# Sheet1.net
KiCad netlist of a schematic drawn in Altium Designer
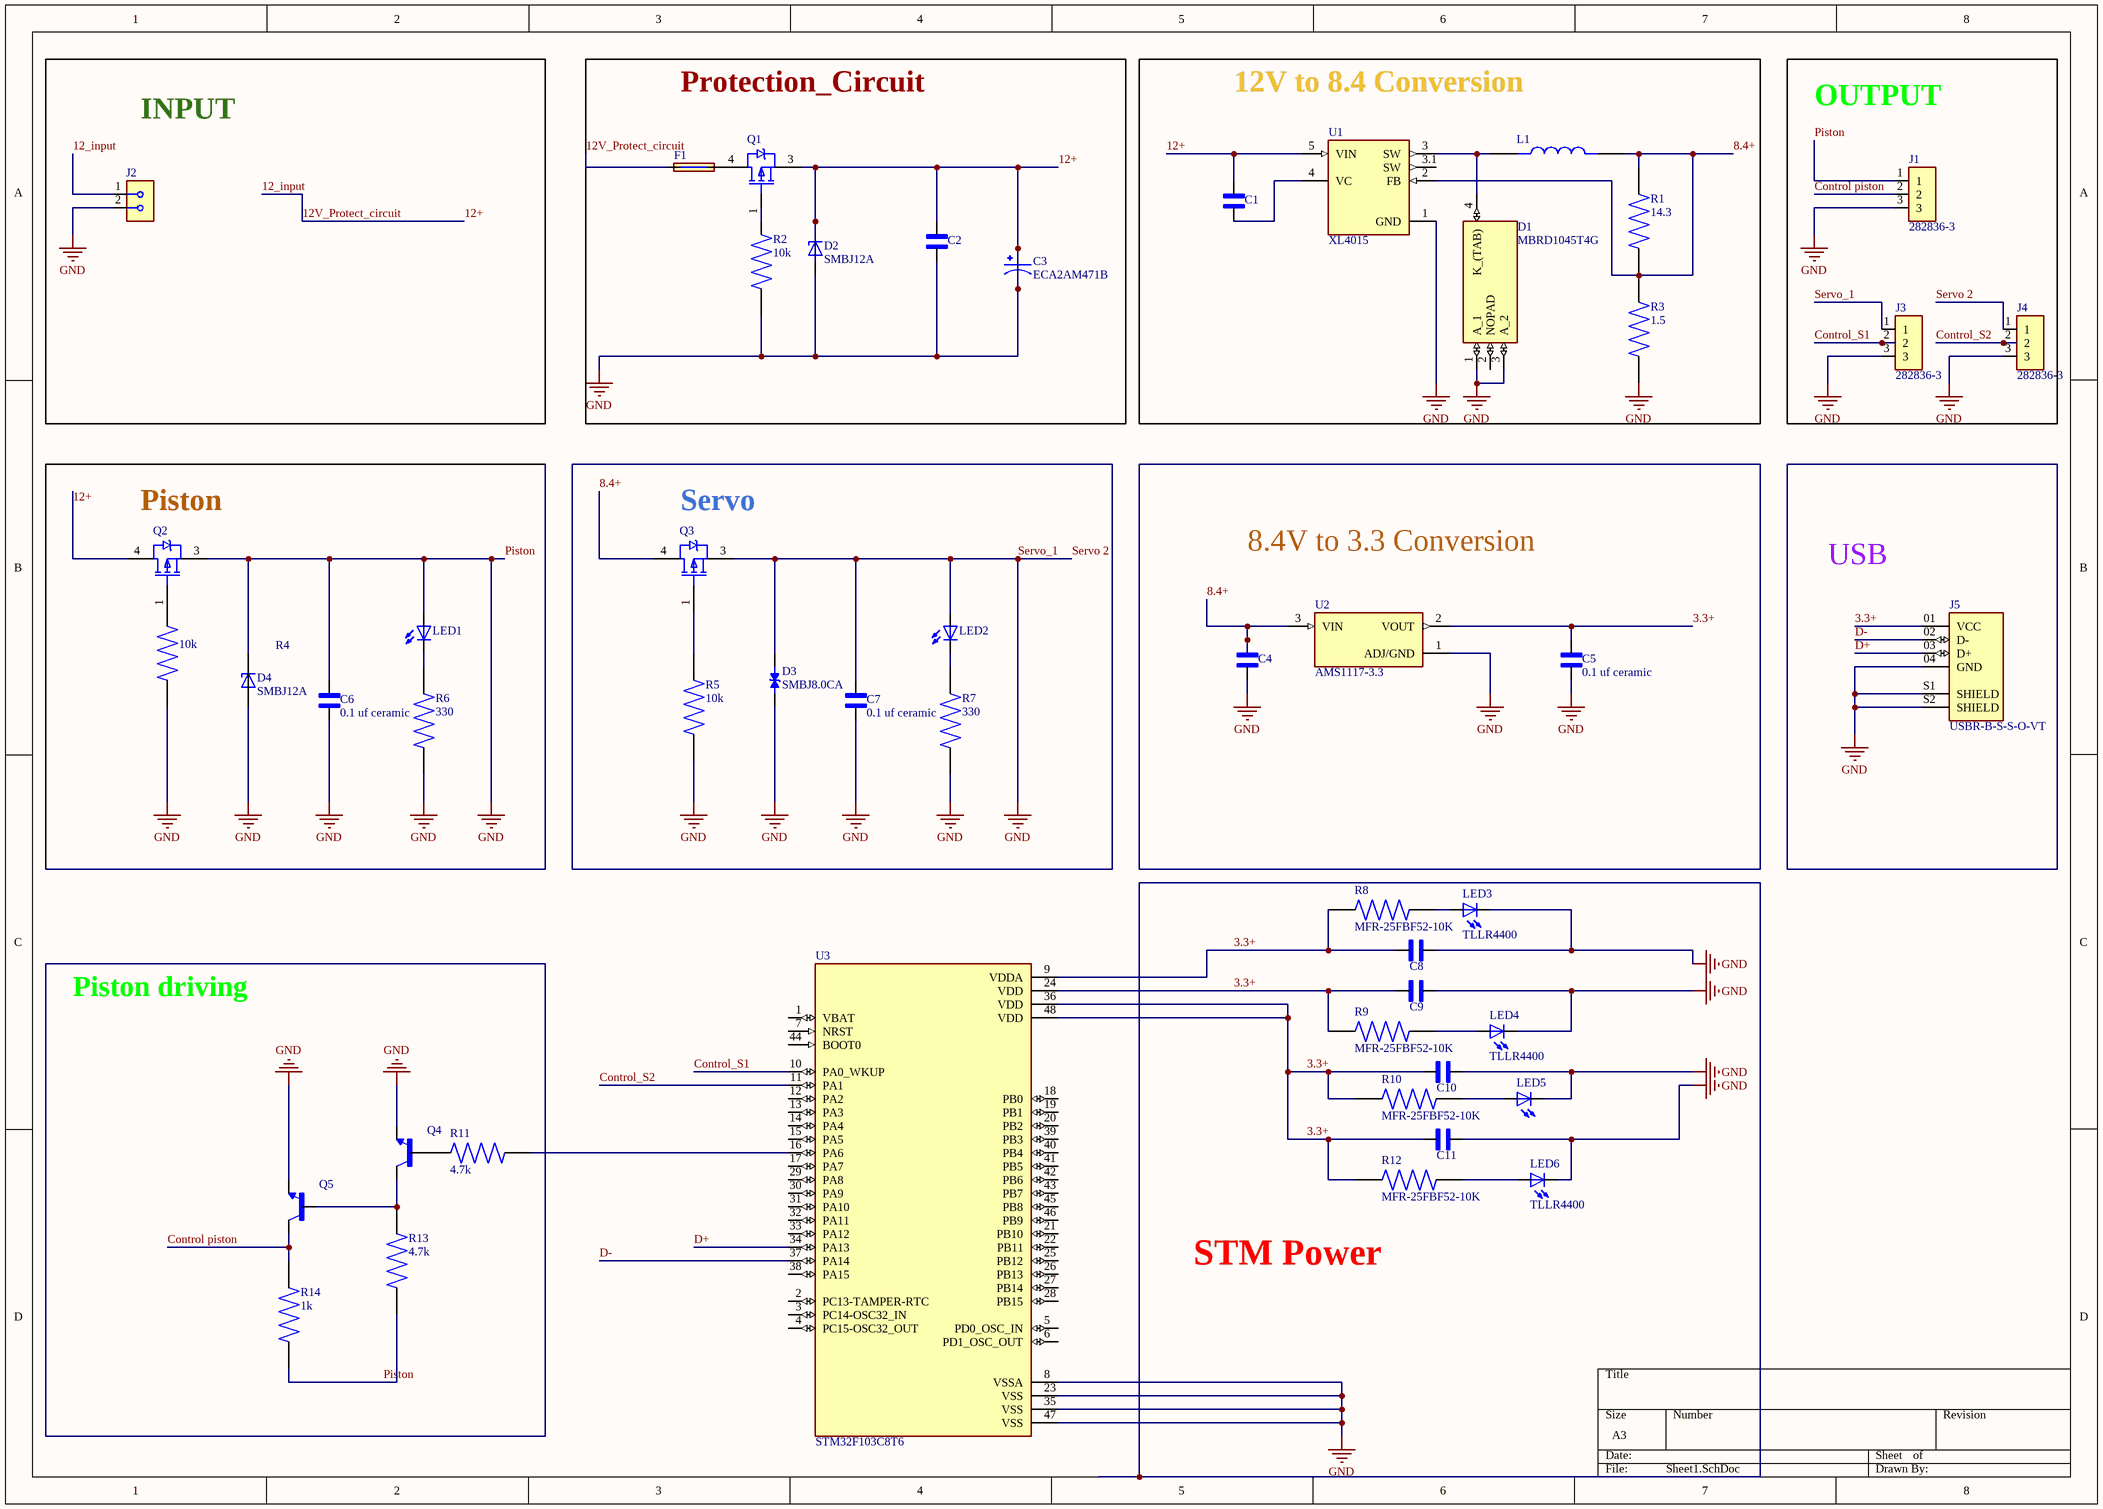
[diagram p0: Sheet1.SchDoc]

(export (version "E")
  (design (tool "Eeschema 10.0.6"))
  (components
    (comp (ref "C1")
      (value "CL10B105KO8NNNC")
      (footprint "CAPC1608X90N")
      (description "1 礔 卤10% 16V Ceramic Capacitor X7R 0603 (1608 Metric)")
      (fields (field (name "MF") "Samsung Electro-Mechanics"))
      (libsource (lib "CL10B105KO8NNNC") (part "CL10B105KO8NNNC"))
    )
    (comp (ref "C2")
      (value "FA14X8R1H104KNU06")
      (footprint "CAPRB250W50L450T300H550")
      (description "0.1 ÂµF Â±10% 50V Ceramic Capacitor X8R Radial")
      (fields (field (name "MF") "TDK"))
      (libsource (lib "FA14X8R1H104KNU06") (part "FA14X8R1H104KNU06"))
    )
    (comp (ref "C3")
      (value "ECA2AM471B")
      (footprint "CAPPRD750W80D1600H2500")
      (description "CAP ALUM 470UF 20% 100V RADIAL")
      (fields (field (name "MF") "Panasonic"))
      (libsource (lib "ECA2AM471B") (part "ECA2AM471B"))
    )
    (comp (ref "C4")
      (value "0.1 uf ceramic")
      (footprint "CAPRB250W50L450T300H550")
      (description "0.1 ÂµF Â±10% 50V Ceramic Capacitor X8R Radial")
      (fields (field (name "MF") "TDK") (field (name "MP") "FA14X8R1H104KNU06"))
      (libsource (lib "FA14X8R1H104KNU06") (part "FA14X8R1H104KNU06"))
    )
    (comp (ref "C5")
      (value "0.1 uf ceramic")
      (footprint "CAPRB250W50L450T300H550")
      (description "0.1 ÂµF Â±10% 50V Ceramic Capacitor X8R Radial")
      (fields (field (name "MF") "TDK") (field (name "MP") "FA14X8R1H104KNU06"))
      (libsource (lib "FA14X8R1H104KNU06") (part "FA14X8R1H104KNU06"))
    )
    (comp (ref "C6")
      (value "0.1 uf ceramic")
      (footprint "CAPRB250W50L450T300H550")
      (description "0.1 ÂµF Â±10% 50V Ceramic Capacitor X8R Radial")
      (fields (field (name "MF") "TDK") (field (name "MP") "FA14X8R1H104KNU06"))
      (libsource (lib "FA14X8R1H104KNU06") (part "FA14X8R1H104KNU06"))
    )
    (comp (ref "C7")
      (value "0.1 uf ceramic")
      (footprint "CAPRB250W50L450T300H550")
      (description "0.1 ÂµF Â±10% 50V Ceramic Capacitor X8R Radial")
      (fields (field (name "MF") "TDK") (field (name "MP") "FA14X8R1H104KNU06"))
      (libsource (lib "FA14X8R1H104KNU06") (part "FA14X8R1H104KNU06"))
    )
    (comp (ref "C8")
      (value "0.1 uf ceramic")
      (footprint "CAPRB250W50L450T300H550")
      (description "0.1 ÂµF Â±10% 50V Ceramic Capacitor X8R Radial")
      (fields (field (name "MF") "TDK") (field (name "MP") "FA14X8R1H104KNU06"))
      (libsource (lib "") (part "FA14X8R1H104KNU06_1"))
    )
    (comp (ref "C9")
      (value "0.1 uf ceramic")
      (footprint "CAPRB250W50L450T300H550")
      (description "0.1 ÂµF Â±10% 50V Ceramic Capacitor X8R Radial")
      (fields (field (name "MF") "TDK") (field (name "MP") "FA14X8R1H104KNU06"))
      (libsource (lib "") (part "FA14X8R1H104KNU06_1"))
    )
    (comp (ref "C10")
      (value "0.1 uf ceramic")
      (footprint "CAPRB250W50L450T300H550")
      (description "0.1 ÂµF Â±10% 50V Ceramic Capacitor X8R Radial")
      (fields (field (name "MF") "TDK") (field (name "MP") "FA14X8R1H104KNU06"))
      (libsource (lib "") (part "FA14X8R1H104KNU06_1"))
    )
    (comp (ref "C11")
      (value "0.1 uf ceramic")
      (footprint "CAPRB250W50L450T300H550")
      (description "0.1 ÂµF Â±10% 50V Ceramic Capacitor X8R Radial")
      (fields (field (name "MF") "TDK") (field (name "MP") "FA14X8R1H104KNU06"))
      (libsource (lib "") (part "FA14X8R1H104KNU06_1"))
    )
    (comp (ref "D1")
      (value "MBRD1045T4G")
      (footprint "TO229P990X238-4N")
      (description "Diode Schottky 45 V 10A Surface Mount DPAK")
      (fields (field (name "MF") "ON Semiconductor"))
      (libsource (lib "MBRD1045T4G (1)") (part "MBRD1045T4G"))
    )
    (comp (ref "D2")
      (value "SMBJ12A")
      (footprint "DIOM4336X265N")
      (description "600W, 14V, 5%, Unidirectional, TVS")
      (fields (field (name "MF") "Taiwan Semiconductor Corporation"))
      (libsource (lib "SMBJ12A") (part "SMBJ12A"))
    )
    (comp (ref "D3")
      (value "SMBJ8.0CA")
      (footprint "DIOM4336X265N")
      (description "600W, 9.4V, 5%, Bidirectional, TVS")
      (fields (field (name "MF") "Taiwan Semiconductor"))
      (libsource (lib "SMBJ8.0CA") (part "SMBJ8.0CA"))
    )
    (comp (ref "D4")
      (value "SMBJ12A")
      (footprint "DIOM4336X265N")
      (description "600W, 14V, 5%, Unidirectional, TVS")
      (fields (field (name "MF") "Taiwan Semiconductor Corporation"))
      (libsource (lib "SMBJ12A") (part "SMBJ12A"))
    )
    (comp (ref "F1")
      (value "0154007.DR")
      (footprint "0154007.DR")
      (fields (field (name "MF") "Littelfuse Inc."))
      (libsource (lib "0154007.DR") (part "0154007.DR"))
    )
    (comp (ref "J1")
      (value "282836-3")
      (footprint "TE_282836-3")
      (description "TERM BLOCK 3POS SIDE ENTRY 5MM")
      (libsource (lib "282836-3") (part "282836-3"))
    )
    (comp (ref "J2")
      (value "OSTTF020161")
      (footprint "OST_OSTTF020161")
      (description "2 Position Wire to Board Terminal Block Vertical with Board 0.138 (3.50mm) Through Hole")
      (fields (field (name "MF") "On Shore"))
      (libsource (lib "OSTTF020161") (part "OSTTF020161"))
    )
    (comp (ref "J3")
      (value "282836-3")
      (footprint "TE_282836-3")
      (description "TERM BLOCK 3POS SIDE ENTRY 5MM")
      (libsource (lib "282836-3") (part "282836-3"))
    )
    (comp (ref "J4")
      (value "282836-3")
      (footprint "TE_282836-3")
      (description "TERM BLOCK 3POS SIDE ENTRY 5MM")
      (libsource (lib "282836-3") (part "282836-3"))
    )
    (comp (ref "J5")
      (value "USBR-B-S-S-O-VT")
      (footprint "SAMTEC_USBR-B-S-S-O-VT")
      (fields (field (name "MF") "Samtec"))
      (libsource (lib "USBR-B-S-S-O-VT") (part "USBR-B-S-S-O-VT"))
    )
    (comp (ref "L1")
      (value "AMDLA1004S-470MT")
      (footprint "IND_AMDLA1004S-470MT")
      (description "FIXED IND 47UH 3.5A 143MOHM SMD")
      (fields (field (name "MF") "Abracon LLC"))
      (libsource (lib "AMDLA1004S-470MT") (part "AMDLA1004S-470MT"))
    )
    (comp (ref "LED1")
      (value "TLLR4400")
      (footprint "LED3MM")
      (description "Red 619nm LED Indication - Discrete 1.9V Radial")
      (fields (field (name "MF") "Vishay"))
      (libsource (lib "TLLR4400") (part "TLLR4400"))
    )
    (comp (ref "LED2")
      (value "TLLR4400")
      (footprint "LED3MM")
      (description "Red 619nm LED Indication - Discrete 1.9V Radial")
      (fields (field (name "MF") "Vishay"))
      (libsource (lib "TLLR4400") (part "TLLR4400"))
    )
    (comp (ref "LED3")
      (value "TLLR4400")
      (footprint "LED3MM")
      (description "Red 619nm LED Indication - Discrete 1.9V Radial")
      (fields (field (name "MF") "Vishay"))
      (libsource (lib "TLLR4400") (part "TLLR4400"))
    )
    (comp (ref "LED4")
      (value "TLLR4400")
      (footprint "LED3MM")
      (description "Red 619nm LED Indication - Discrete 1.9V Radial")
      (fields (field (name "MF") "Vishay"))
      (libsource (lib "TLLR4400") (part "TLLR4400"))
    )
    (comp (ref "LED5")
      (value "TLLR4400")
      (footprint "LED3MM")
      (description "Red 619nm LED Indication - Discrete 1.9V Radial")
      (fields (field (name "MF") "Vishay"))
      (libsource (lib "TLLR4400") (part "TLLR4400"))
    )
    (comp (ref "LED6")
      (value "TLLR4400")
      (footprint "LED3MM")
      (description "Red 619nm LED Indication - Discrete 1.9V Radial")
      (fields (field (name "MF") "Vishay"))
      (libsource (lib "TLLR4400") (part "TLLR4400"))
    )
    (comp (ref "Q1")
      (value "MTB50P03HDLT4G")
      (footprint "ONSC-D2PAK-3-418B-04_V")
      (description "P-Channel 30 V 50A (Tc) 2.5W (Ta), 125W (Tc) Surface Mount DÂ²PAK")
      (fields (field (name "MF") "ON Semiconductor"))
      (libsource (lib "MTB50P03HDLT4G") (part "MTB50P03HDLT4G"))
    )
    (comp (ref "Q2")
      (value "MTB50P03HDLT4G")
      (footprint "ONSC-D2PAK-3-418B-04_V")
      (description "P-Channel 30 V 50A (Tc) 2.5W (Ta), 125W (Tc) Surface Mount DÂ²PAK")
      (fields (field (name "MF") "ON Semiconductor"))
      (libsource (lib "MTB50P03HDLT4G") (part "MTB50P03HDLT4G"))
    )
    (comp (ref "Q3")
      (value "MTB50P03HDLT4G")
      (footprint "ONSC-D2PAK-3-418B-04_V")
      (description "P-Channel 30 V 50A (Tc) 2.5W (Ta), 125W (Tc) Surface Mount DÂ²PAK")
      (fields (field (name "MF") "ON Semiconductor"))
      (libsource (lib "MTB50P03HDLT4G") (part "MTB50P03HDLT4G"))
    )
    (comp (ref "Q4")
      (value "2N3904")
      (footprint "TO92254P460H750-3")
      (description "BJT, TO-92, 40V, 200mA, NPN, 0.625W, 150Â°C")
      (fields (field (name "MF") "Diotec Semiconductor"))
      (libsource (lib "2N3904") (part "2N3904"))
    )
    (comp (ref "Q5")
      (value "2N3904")
      (footprint "TO92254P460H750-3")
      (description "BJT, TO-92, 40V, 200mA, NPN, 0.625W, 150Â°C")
      (fields (field (name "MF") "Diotec Semiconductor"))
      (libsource (lib "2N3904") (part "2N3904"))
    )
    (comp (ref "R1")
      (value "14.3")
      (footprint "RESAD1100W55L680D260")
      (description "10.2 kOhms Â±1% 0.25W, 1/4W Through Hole Resistor Axial - Metal Film")
      (fields (field (name "MF") "Yageo") (field (name "MP") "MFR-25FBF52-10K"))
      (libsource (lib "MFR-25FBF52-10K") (part "MFR-25FBF52-10K"))
    )
    (comp (ref "R2")
      (value "10k")
      (footprint "RESAD1100W55L680D260")
      (description "10.2 kOhms Â±1% 0.25W, 1/4W Through Hole Resistor Axial - Metal Film")
      (fields (field (name "MF") "Yageo") (field (name "MP") "MFR-25FBF52-10K"))
      (libsource (lib "MFR-25FBF52-10K") (part "MFR-25FBF52-10K"))
    )
    (comp (ref "R3")
      (value "1.5")
      (footprint "RESAD1100W55L680D260")
      (description "10.2 kOhms Â±1% 0.25W, 1/4W Through Hole Resistor Axial - Metal Film")
      (fields (field (name "MF") "Yageo") (field (name "MP") "MFR-25FBF52-10K"))
      (libsource (lib "MFR-25FBF52-10K") (part "MFR-25FBF52-10K"))
    )
    (comp (ref "R4")
      (value "10k")
      (footprint "RESAD1100W55L680D260")
      (description "10.2 kOhms Â±1% 0.25W, 1/4W Through Hole Resistor Axial - Metal Film")
      (fields (field (name "MF") "Yageo") (field (name "MP") "MFR-25FBF52-10K"))
      (libsource (lib "MFR-25FBF52-10K") (part "MFR-25FBF52-10K"))
    )
    (comp (ref "R5")
      (value "10k")
      (footprint "RESAD1100W55L680D260")
      (description "10.2 kOhms Â±1% 0.25W, 1/4W Through Hole Resistor Axial - Metal Film")
      (fields (field (name "MF") "Yageo") (field (name "MP") "MFR-25FBF52-10K"))
      (libsource (lib "MFR-25FBF52-10K") (part "MFR-25FBF52-10K"))
    )
    (comp (ref "R6")
      (value "330")
      (footprint "RESAD1100W55L680D260")
      (description "10.2 kOhms Â±1% 0.25W, 1/4W Through Hole Resistor Axial - Metal Film")
      (fields (field (name "MF") "Yageo") (field (name "MP") "MFR-25FBF52-10K"))
      (libsource (lib "MFR-25FBF52-10K") (part "MFR-25FBF52-10K"))
    )
    (comp (ref "R7")
      (value "330")
      (footprint "RESAD1100W55L680D260")
      (description "10.2 kOhms Â±1% 0.25W, 1/4W Through Hole Resistor Axial - Metal Film")
      (fields (field (name "MF") "Yageo") (field (name "MP") "MFR-25FBF52-10K"))
      (libsource (lib "MFR-25FBF52-10K") (part "MFR-25FBF52-10K"))
    )
    (comp (ref "R8")
      (value "MFR-25FBF52-10K")
      (footprint "RESAD1100W55L680D260")
      (description "10.2 kOhms Â±1% 0.25W, 1/4W Through Hole Resistor Axial - Metal Film")
      (fields (field (name "MF") "Yageo"))
      (libsource (lib "MFR-25FBF52-10K") (part "MFR-25FBF52-10K"))
    )
    (comp (ref "R9")
      (value "MFR-25FBF52-10K")
      (footprint "RESAD1100W55L680D260")
      (description "10.2 kOhms Â±1% 0.25W, 1/4W Through Hole Resistor Axial - Metal Film")
      (fields (field (name "MF") "Yageo"))
      (libsource (lib "MFR-25FBF52-10K") (part "MFR-25FBF52-10K"))
    )
    (comp (ref "R10")
      (value "MFR-25FBF52-10K")
      (footprint "RESAD1100W55L680D260")
      (description "10.2 kOhms Â±1% 0.25W, 1/4W Through Hole Resistor Axial - Metal Film")
      (fields (field (name "MF") "Yageo"))
      (libsource (lib "MFR-25FBF52-10K") (part "MFR-25FBF52-10K"))
    )
    (comp (ref "R11")
      (value "4.7k")
      (footprint "RESAD1100W55L680D260")
      (description "10.2 kOhms Â±1% 0.25W, 1/4W Through Hole Resistor Axial - Metal Film")
      (fields (field (name "MF") "Yageo") (field (name "MP") "MFR-25FBF52-10K"))
      (libsource (lib "MFR-25FBF52-10K") (part "MFR-25FBF52-10K"))
    )
    (comp (ref "R12")
      (value "MFR-25FBF52-10K")
      (footprint "RESAD1100W55L680D260")
      (description "10.2 kOhms Â±1% 0.25W, 1/4W Through Hole Resistor Axial - Metal Film")
      (fields (field (name "MF") "Yageo"))
      (libsource (lib "MFR-25FBF52-10K") (part "MFR-25FBF52-10K"))
    )
    (comp (ref "R13")
      (value "4.7k")
      (footprint "RESAD1100W55L680D260")
      (description "10.2 kOhms Â±1% 0.25W, 1/4W Through Hole Resistor Axial - Metal Film")
      (fields (field (name "MF") "Yageo") (field (name "MP") "MFR-25FBF52-10K"))
      (libsource (lib "MFR-25FBF52-10K") (part "MFR-25FBF52-10K"))
    )
    (comp (ref "R14")
      (value "1k")
      (footprint "RESAD1100W55L680D260")
      (description "10.2 kOhms Â±1% 0.25W, 1/4W Through Hole Resistor Axial - Metal Film")
      (fields (field (name "MF") "Yageo") (field (name "MP") "MFR-25FBF52-10K"))
      (libsource (lib "MFR-25FBF52-10K") (part "MFR-25FBF52-10K"))
    )
    (comp (ref "U1")
      (value "XL4015")
      (footprint "CONV_XL4015")
      (description "5A 180KHz 36V Buck DC to DC Converter")
      (fields (field (name "MF") "XLSEMI"))
      (libsource (lib "XL4015") (part "XL4015"))
    )
    (comp (ref "U2")
      (value "AMS1117-3.3")
      (footprint "SOT229P700X180-4N")
      (description "Linear Voltage Regulator IC Positive Fixed 1 Output 1A SOT-223-3L")
      (fields (field (name "MF") "UMW"))
      (libsource (lib "AMS1117-3.3") (part "AMS1117-3.3"))
    )
    (comp (ref "U3")
      (value "STM32F103C8T6")
      (footprint "QFP50P900X900X160-48N")
      (description "ARM® Cortex®-M3 STM32F1 Microcontroller IC 32-Bit 72MHz 64KB (64K x 8) FLASH 48-LQFP (7x7)")
      (fields (field (name "MF") "STMicroelectronics"))
      (libsource (lib "STM32F103C8T6") (part "STM32F103C8T6"))
    )
  )
  (nets
    (net (code "1") (name "/3.3+") (class "Default")
      (node (ref "C10") (pin "2") (pinfunction "2_2") (pintype "passive"))
      (node (ref "C11") (pin "2") (pinfunction "2_2") (pintype "passive"))
      (node (ref "C5") (pin "2") (pinfunction "2_2") (pintype "passive"))
      (node (ref "C8") (pin "2") (pinfunction "2_2") (pintype "passive"))
      (node (ref "C9") (pin "2") (pinfunction "2_2") (pintype "passive"))
      (node (ref "J5") (pin "01") (pinfunction "VCC_01") (pintype "power_in"))
      (node (ref "R10") (pin "1") (pinfunction "1_1") (pintype "passive"))
      (node (ref "R12") (pin "1") (pinfunction "1_1") (pintype "passive"))
      (node (ref "R8") (pin "1") (pinfunction "1_1") (pintype "passive"))
      (node (ref "R9") (pin "1") (pinfunction "1_1") (pintype "passive"))
      (node (ref "U2") (pin "2") (pinfunction "VOUT_2") (pintype "output"))
      (node (ref "U3") (pin "24") (pinfunction "VDD_24") (pintype "power_in"))
      (node (ref "U3") (pin "36") (pinfunction "VDD_36") (pintype "power_in"))
      (node (ref "U3") (pin "48") (pinfunction "VDD_48") (pintype "power_in"))
      (node (ref "U3") (pin "9") (pinfunction "VDDA_9") (pintype "power_in"))
    )
    (net (code "2") (name "/8.4+") (class "Default")
      (node (ref "C4") (pin "2") (pinfunction "2_2") (pintype "passive"))
      (node (ref "L1") (pin "2") (pinfunction "2_2") (pintype "passive"))
      (node (ref "Q3") (pin "4") (pinfunction "D_4") (pintype "passive"))
      (node (ref "R1") (pin "1") (pinfunction "1_1") (pintype "passive"))
      (node (ref "R1") (pin "2") (pinfunction "2_2") (pintype "passive"))
      (node (ref "R3") (pin "2") (pinfunction "2_2") (pintype "passive"))
      (node (ref "U1") (pin "2") (pinfunction "FB_2") (pintype "input"))
      (node (ref "U2") (pin "3") (pinfunction "VIN_3") (pintype "input"))
    )
    (net (code "3") (name "/Control piston") (class "Default")
      (node (ref "J1") (pin "2") (pinfunction "2_2") (pintype "passive"))
      (node (ref "Q5") (pin "3") (pinfunction "C_3") (pintype "passive"))
      (node (ref "R14") (pin "2") (pinfunction "2_2") (pintype "passive"))
    )
    (net (code "4") (name "/Control_S1") (class "Default")
      (node (ref "J3") (pin "2") (pinfunction "2_2") (pintype "passive"))
      (node (ref "U3") (pin "10") (pinfunction "PA0_WKUP_10") (pintype "bidirectional"))
    )
    (net (code "5") (name "/Control_S2") (class "Default")
      (node (ref "J4") (pin "2") (pinfunction "2_2") (pintype "passive"))
      (node (ref "U3") (pin "11") (pinfunction "PA1_11") (pintype "bidirectional"))
    )
    (net (code "6") (name "/D+") (class "Default")
      (node (ref "J5") (pin "03") (pinfunction "D+_03") (pintype "bidirectional"))
      (node (ref "U3") (pin "34") (pinfunction "PA13_34") (pintype "bidirectional"))
    )
    (net (code "7") (name "/D-") (class "Default")
      (node (ref "J5") (pin "02") (pinfunction "D-_02") (pintype "bidirectional"))
      (node (ref "U3") (pin "37") (pinfunction "PA14_37") (pintype "bidirectional"))
    )
    (net (code "8") (name "GND") (class "Default")
      (node (ref "C1") (pin "2") (pinfunction "2_2") (pintype "passive"))
      (node (ref "C10") (pin "1") (pinfunction "1_1") (pintype "passive"))
      (node (ref "C11") (pin "1") (pinfunction "1_1") (pintype "passive"))
      (node (ref "C2") (pin "1") (pinfunction "1_1") (pintype "passive"))
      (node (ref "C2") (pin "2") (pinfunction "2_2") (pintype "passive"))
      (node (ref "C3") (pin "N") (pinfunction "N_N") (pintype "passive"))
      (node (ref "C3") (pin "P") (pinfunction "P_P") (pintype "passive"))
      (node (ref "C4") (pin "1") (pinfunction "1_1") (pintype "passive"))
      (node (ref "C5") (pin "1") (pinfunction "1_1") (pintype "passive"))
      (node (ref "C6") (pin "1") (pinfunction "1_1") (pintype "passive"))
      (node (ref "C6") (pin "2") (pinfunction "2_2") (pintype "passive"))
      (node (ref "C7") (pin "1") (pinfunction "1_1") (pintype "passive"))
      (node (ref "C7") (pin "2") (pinfunction "2_2") (pintype "passive"))
      (node (ref "C8") (pin "1") (pinfunction "1_1") (pintype "passive"))
      (node (ref "C9") (pin "1") (pinfunction "1_1") (pintype "passive"))
      (node (ref "D1") (pin "1") (pinfunction "A_1_1") (pintype "bidirectional"))
      (node (ref "D1") (pin "3") (pinfunction "A_2_3") (pintype "bidirectional"))
      (node (ref "D2") (pin "A") (pinfunction "A_A") (pintype "passive"))
      (node (ref "D2") (pin "C") (pinfunction "C_C") (pintype "passive"))
      (node (ref "D3") (pin "1") (pinfunction "1_1") (pintype "passive"))
      (node (ref "D3") (pin "2") (pinfunction "2_2") (pintype "passive"))
      (node (ref "D4") (pin "A") (pinfunction "A_A") (pintype "passive"))
      (node (ref "D4") (pin "C") (pinfunction "C_C") (pintype "passive"))
      (node (ref "F1") (pin "1") (pinfunction "1_1") (pintype "passive"))
      (node (ref "J1") (pin "1") (pinfunction "1_1") (pintype "passive"))
      (node (ref "J1") (pin "3") (pinfunction "3_3") (pintype "passive"))
      (node (ref "J2") (pin "1") (pinfunction "1_1") (pintype "passive"))
      (node (ref "J2") (pin "2") (pinfunction "2_2") (pintype "passive"))
      (node (ref "J3") (pin "1") (pinfunction "1_1") (pintype "passive"))
      (node (ref "J3") (pin "3") (pinfunction "3_3") (pintype "passive"))
      (node (ref "J4") (pin "1") (pinfunction "1_1") (pintype "passive"))
      (node (ref "J4") (pin "3") (pinfunction "3_3") (pintype "passive"))
      (node (ref "J5") (pin "04") (pinfunction "GND_04") (pintype "power_in"))
      (node (ref "J5") (pin "S1") (pinfunction "SHIELD_S1") (pintype "passive"))
      (node (ref "J5") (pin "S2") (pinfunction "SHIELD_S2") (pintype "passive"))
      (node (ref "LED1") (pin "A") (pinfunction "A_A") (pintype "passive"))
      (node (ref "LED2") (pin "A") (pinfunction "A_A") (pintype "passive"))
      (node (ref "LED3") (pin "K") (pinfunction "C_K") (pintype "passive"))
      (node (ref "LED4") (pin "K") (pinfunction "C_K") (pintype "passive"))
      (node (ref "LED5") (pin "K") (pinfunction "C_K") (pintype "passive"))
      (node (ref "LED6") (pin "K") (pinfunction "C_K") (pintype "passive"))
      (node (ref "Q1") (pin "3") (pinfunction "S_3") (pintype "passive"))
      (node (ref "Q2") (pin "3") (pinfunction "S_3") (pintype "passive"))
      (node (ref "Q2") (pin "4") (pinfunction "D_4") (pintype "passive"))
      (node (ref "Q3") (pin "3") (pinfunction "S_3") (pintype "passive"))
      (node (ref "Q4") (pin "1") (pinfunction "E_1") (pintype "passive"))
      (node (ref "Q5") (pin "1") (pinfunction "E_1") (pintype "passive"))
      (node (ref "R13") (pin "1") (pinfunction "1_1") (pintype "passive"))
      (node (ref "R14") (pin "1") (pinfunction "1_1") (pintype "passive"))
      (node (ref "R2") (pin "1") (pinfunction "1_1") (pintype "passive"))
      (node (ref "R3") (pin "1") (pinfunction "1_1") (pintype "passive"))
      (node (ref "R4") (pin "1") (pinfunction "1_1") (pintype "passive"))
      (node (ref "R5") (pin "1") (pinfunction "1_1") (pintype "passive"))
      (node (ref "R6") (pin "1") (pinfunction "1_1") (pintype "passive"))
      (node (ref "R7") (pin "1") (pinfunction "1_1") (pintype "passive"))
      (node (ref "U1") (pin "1") (pinfunction "GND_1") (pintype "power_in"))
      (node (ref "U1") (pin "5") (pinfunction "VIN_5") (pintype "input"))
      (node (ref "U2") (pin "1") (pinfunction "ADJ/GND_1") (pintype "power_in"))
      (node (ref "U3") (pin "23") (pinfunction "VSS_23") (pintype "power_in"))
      (node (ref "U3") (pin "35") (pinfunction "VSS_35") (pintype "power_in"))
      (node (ref "U3") (pin "47") (pinfunction "VSS_47") (pintype "power_in"))
      (node (ref "U3") (pin "8") (pinfunction "VSSA_8") (pintype "power_in"))
    )
    (net (code "9") (name "Net-(D1-K_(TAB))") (class "Default")
      (node (ref "D1") (pin "4") (pinfunction "K_(TAB)_4") (pintype "bidirectional"))
      (node (ref "L1") (pin "1") (pinfunction "1_1") (pintype "passive"))
      (node (ref "U1") (pin "3") (pinfunction "SW_3") (pintype "output"))
    )
    (net (code "10") (name "Net-(LED1-C)") (class "Default")
      (node (ref "LED1") (pin "K") (pinfunction "C_K") (pintype "passive"))
      (node (ref "R6") (pin "2") (pinfunction "2_2") (pintype "passive"))
    )
    (net (code "11") (name "Net-(LED2-C)") (class "Default")
      (node (ref "LED2") (pin "K") (pinfunction "C_K") (pintype "passive"))
      (node (ref "R7") (pin "2") (pinfunction "2_2") (pintype "passive"))
    )
    (net (code "12") (name "Net-(LED3-PadA)") (class "Default")
      (node (ref "LED3") (pin "A") (pinfunction "A_A") (pintype "passive"))
      (node (ref "R8") (pin "2") (pinfunction "2_2") (pintype "passive"))
    )
    (net (code "13") (name "Net-(LED4-PadA)") (class "Default")
      (node (ref "LED4") (pin "A") (pinfunction "A_A") (pintype "passive"))
      (node (ref "R9") (pin "2") (pinfunction "2_2") (pintype "passive"))
    )
    (net (code "14") (name "Net-(LED5-PadA)") (class "Default")
      (node (ref "LED5") (pin "A") (pinfunction "A_A") (pintype "passive"))
      (node (ref "R10") (pin "2") (pinfunction "2_2") (pintype "passive"))
    )
    (net (code "15") (name "Net-(LED6-PadA)") (class "Default")
      (node (ref "LED6") (pin "A") (pinfunction "A_A") (pintype "passive"))
      (node (ref "R12") (pin "2") (pinfunction "2_2") (pintype "passive"))
    )
    (net (code "16") (name "Net-(Q1-D)") (class "Default")
      (node (ref "F1") (pin "2") (pinfunction "2_2") (pintype "passive"))
      (node (ref "Q1") (pin "4") (pinfunction "D_4") (pintype "passive"))
    )
    (net (code "17") (name "Net-(Q1-G)") (class "Default")
      (node (ref "Q1") (pin "1") (pinfunction "G_1") (pintype "passive"))
      (node (ref "R2") (pin "2") (pinfunction "2_2") (pintype "passive"))
    )
    (net (code "18") (name "Net-(Q3-G)") (class "Default")
      (node (ref "Q3") (pin "1") (pinfunction "G_1") (pintype "passive"))
      (node (ref "R5") (pin "2") (pinfunction "2_2") (pintype "passive"))
    )
    (net (code "19") (name "Net-(Q4-B)") (class "Default")
      (node (ref "Q4") (pin "2") (pinfunction "B_2") (pintype "passive"))
      (node (ref "R11") (pin "1") (pinfunction "1_1") (pintype "passive"))
    )
    (net (code "20") (name "Net-(Q4-C)") (class "Default")
      (node (ref "Q4") (pin "3") (pinfunction "C_3") (pintype "passive"))
      (node (ref "Q5") (pin "2") (pinfunction "B_2") (pintype "passive"))
      (node (ref "R13") (pin "2") (pinfunction "2_2") (pintype "passive"))
    )
    (net (code "21") (name "Net-(U1-VC)") (class "Default")
      (node (ref "C1") (pin "1") (pinfunction "1_1") (pintype "passive"))
      (node (ref "U1") (pin "4") (pinfunction "VC_4") (pintype "passive"))
    )
    (net (code "22") (name "Net-(U3-PA6)") (class "Default")
      (node (ref "R11") (pin "2") (pinfunction "2_2") (pintype "passive"))
      (node (ref "U3") (pin "16") (pinfunction "PA6_16") (pintype "bidirectional"))
    )
    (net (code "23") (name "unconnected-(D1-NOPAD-Pad2)") (class "Default")
      (node (ref "D1") (pin "2") (pinfunction "NOPAD_2") (pintype "bidirectional"))
    )
    (net (code "24") (name "unconnected-(Q2-G-Pad1)") (class "Default")
      (node (ref "Q2") (pin "1") (pinfunction "G_1") (pintype "passive"))
    )
    (net (code "25") (name "unconnected-(R4-Pad2)") (class "Default")
      (node (ref "R4") (pin "2") (pinfunction "2_2") (pintype "passive"))
    )
    (net (code "26") (name "unconnected-(U1-SW-Pad3.1)") (class "Default")
      (node (ref "U1") (pin "3.1") (pinfunction "SW_3.1") (pintype "output"))
    )
    (net (code "27") (name "unconnected-(U3-BOOT0-Pad44)") (class "Default")
      (node (ref "U3") (pin "44") (pinfunction "BOOT0_44") (pintype "input"))
    )
    (net (code "28") (name "unconnected-(U3-NRST-Pad7)") (class "Default")
      (node (ref "U3") (pin "7") (pinfunction "NRST_7") (pintype "input"))
    )
    (net (code "29") (name "unconnected-(U3-PA2-Pad12)") (class "Default")
      (node (ref "U3") (pin "12") (pinfunction "PA2_12") (pintype "bidirectional"))
    )
    (net (code "30") (name "unconnected-(U3-PA3-Pad13)") (class "Default")
      (node (ref "U3") (pin "13") (pinfunction "PA3_13") (pintype "bidirectional"))
    )
    (net (code "31") (name "unconnected-(U3-PA4-Pad14)") (class "Default")
      (node (ref "U3") (pin "14") (pinfunction "PA4_14") (pintype "bidirectional"))
    )
    (net (code "32") (name "unconnected-(U3-PA5-Pad15)") (class "Default")
      (node (ref "U3") (pin "15") (pinfunction "PA5_15") (pintype "bidirectional"))
    )
    (net (code "33") (name "unconnected-(U3-PA7-Pad17)") (class "Default")
      (node (ref "U3") (pin "17") (pinfunction "PA7_17") (pintype "bidirectional"))
    )
    (net (code "34") (name "unconnected-(U3-PA8-Pad29)") (class "Default")
      (node (ref "U3") (pin "29") (pinfunction "PA8_29") (pintype "bidirectional"))
    )
    (net (code "35") (name "unconnected-(U3-PA9-Pad30)") (class "Default")
      (node (ref "U3") (pin "30") (pinfunction "PA9_30") (pintype "bidirectional"))
    )
    (net (code "36") (name "unconnected-(U3-PA10-Pad31)") (class "Default")
      (node (ref "U3") (pin "31") (pinfunction "PA10_31") (pintype "bidirectional"))
    )
    (net (code "37") (name "unconnected-(U3-PA11-Pad32)") (class "Default")
      (node (ref "U3") (pin "32") (pinfunction "PA11_32") (pintype "bidirectional"))
    )
    (net (code "38") (name "unconnected-(U3-PA12-Pad33)") (class "Default")
      (node (ref "U3") (pin "33") (pinfunction "PA12_33") (pintype "bidirectional"))
    )
    (net (code "39") (name "unconnected-(U3-PA15-Pad38)") (class "Default")
      (node (ref "U3") (pin "38") (pinfunction "PA15_38") (pintype "bidirectional"))
    )
    (net (code "40") (name "unconnected-(U3-PB0-Pad18)") (class "Default")
      (node (ref "U3") (pin "18") (pinfunction "PB0_18") (pintype "bidirectional"))
    )
    (net (code "41") (name "unconnected-(U3-PB1-Pad19)") (class "Default")
      (node (ref "U3") (pin "19") (pinfunction "PB1_19") (pintype "bidirectional"))
    )
    (net (code "42") (name "unconnected-(U3-PB2-Pad20)") (class "Default")
      (node (ref "U3") (pin "20") (pinfunction "PB2_20") (pintype "bidirectional"))
    )
    (net (code "43") (name "unconnected-(U3-PB3-Pad39)") (class "Default")
      (node (ref "U3") (pin "39") (pinfunction "PB3_39") (pintype "bidirectional"))
    )
    (net (code "44") (name "unconnected-(U3-PB4-Pad40)") (class "Default")
      (node (ref "U3") (pin "40") (pinfunction "PB4_40") (pintype "bidirectional"))
    )
    (net (code "45") (name "unconnected-(U3-PB5-Pad41)") (class "Default")
      (node (ref "U3") (pin "41") (pinfunction "PB5_41") (pintype "bidirectional"))
    )
    (net (code "46") (name "unconnected-(U3-PB6-Pad42)") (class "Default")
      (node (ref "U3") (pin "42") (pinfunction "PB6_42") (pintype "bidirectional"))
    )
    (net (code "47") (name "unconnected-(U3-PB7-Pad43)") (class "Default")
      (node (ref "U3") (pin "43") (pinfunction "PB7_43") (pintype "bidirectional"))
    )
    (net (code "48") (name "unconnected-(U3-PB8-Pad45)") (class "Default")
      (node (ref "U3") (pin "45") (pinfunction "PB8_45") (pintype "bidirectional"))
    )
    (net (code "49") (name "unconnected-(U3-PB9-Pad46)") (class "Default")
      (node (ref "U3") (pin "46") (pinfunction "PB9_46") (pintype "bidirectional"))
    )
    (net (code "50") (name "unconnected-(U3-PB10-Pad21)") (class "Default")
      (node (ref "U3") (pin "21") (pinfunction "PB10_21") (pintype "bidirectional"))
    )
    (net (code "51") (name "unconnected-(U3-PB11-Pad22)") (class "Default")
      (node (ref "U3") (pin "22") (pinfunction "PB11_22") (pintype "bidirectional"))
    )
    (net (code "52") (name "unconnected-(U3-PB12-Pad25)") (class "Default")
      (node (ref "U3") (pin "25") (pinfunction "PB12_25") (pintype "bidirectional"))
    )
    (net (code "53") (name "unconnected-(U3-PB13-Pad26)") (class "Default")
      (node (ref "U3") (pin "26") (pinfunction "PB13_26") (pintype "bidirectional"))
    )
    (net (code "54") (name "unconnected-(U3-PB14-Pad27)") (class "Default")
      (node (ref "U3") (pin "27") (pinfunction "PB14_27") (pintype "bidirectional"))
    )
    (net (code "55") (name "unconnected-(U3-PB15-Pad28)") (class "Default")
      (node (ref "U3") (pin "28") (pinfunction "PB15_28") (pintype "bidirectional"))
    )
    (net (code "56") (name "unconnected-(U3-PC13-TAMPER-RTC-Pad2)") (class "Default")
      (node (ref "U3") (pin "2") (pinfunction "PC13-TAMPER-RTC_2") (pintype "bidirectional"))
    )
    (net (code "57") (name "unconnected-(U3-PC14-OSC32_IN-Pad3)") (class "Default")
      (node (ref "U3") (pin "3") (pinfunction "PC14-OSC32_IN_3") (pintype "bidirectional"))
    )
    (net (code "58") (name "unconnected-(U3-PC15-OSC32_OUT-Pad4)") (class "Default")
      (node (ref "U3") (pin "4") (pinfunction "PC15-OSC32_OUT_4") (pintype "bidirectional"))
    )
    (net (code "59") (name "unconnected-(U3-PD0_OSC_IN-Pad5)") (class "Default")
      (node (ref "U3") (pin "5") (pinfunction "PD0_OSC_IN_5") (pintype "bidirectional"))
    )
    (net (code "60") (name "unconnected-(U3-PD1_OSC_OUT-Pad6)") (class "Default")
      (node (ref "U3") (pin "6") (pinfunction "PD1_OSC_OUT_6") (pintype "bidirectional"))
    )
    (net (code "61") (name "unconnected-(U3-VBAT-Pad1)") (class "Default")
      (node (ref "U3") (pin "1") (pinfunction "VBAT_1") (pintype "bidirectional"))
    )
  )
)
